# Converter_Dif-Se.net
KiCad netlist of a schematic drawn in Altium Designer
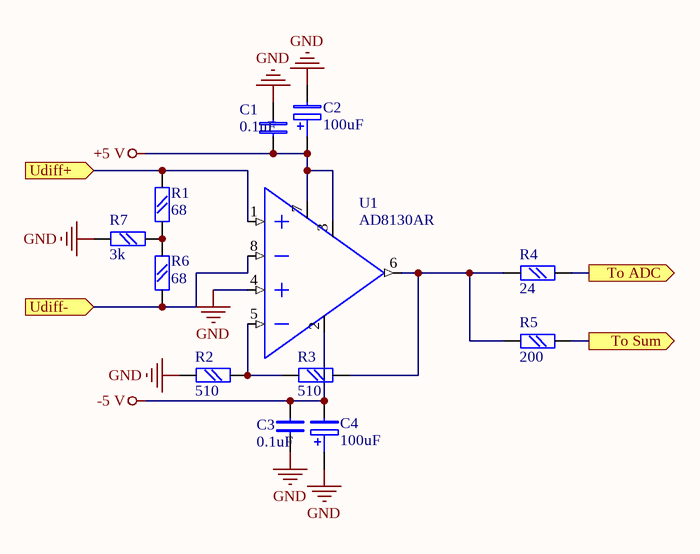
[diagram p0: Converter_Dif-Se.SchDoc]

(export (version "E")
  (design (tool "Eeschema 10.0.6"))
  (components
    (comp (ref "C1") (value "0.1uF") (footprint "chip0805") (libsource (lib "vDevice") (part "C")))
    (comp (ref "C2") (value "100uF") (footprint "CEL-SMD300") (libsource (lib "vDevice") (part "C POL")))
    (comp (ref "C3") (value "0.1uF") (footprint "chip0805") (libsource (lib "vDevice") (part "C")))
    (comp (ref "C4") (value "100uF") (footprint "CEL-SMD300") (libsource (lib "vDevice") (part "C POL")))
    (comp (ref "R1") (value "68") (footprint "chip0805") (libsource (lib "vDevice") (part "R")))
    (comp (ref "R2") (value "510") (footprint "chip0805") (libsource (lib "vDevice") (part "R")))
    (comp (ref "R3") (value "510") (footprint "chip0805") (libsource (lib "vDevice") (part "R")))
    (comp (ref "R4") (value "24") (footprint "chip0805") (libsource (lib "vDevice") (part "R")))
    (comp (ref "R5") (value "200") (footprint "chip0805") (libsource (lib "vDevice") (part "R")))
    (comp (ref "R6") (value "68") (footprint "chip0805") (libsource (lib "vDevice") (part "R")))
    (comp (ref "R7") (value "3k") (footprint "chip0805") (libsource (lib "vDevice") (part "R")))
    (comp (ref "U1") (value "AD8130AR") (footprint "SO-8") (libsource (lib "vAnalog") (part "AD8130")))
  )
  (nets
    (net (code "1") (name "+5 V") (class "Default")
      (node (ref "C1") (pin "2") (pinfunction "2_2") (pintype "passive"))
      (node (ref "C2") (pin "+") (pinfunction "+_+") (pintype "passive"))
      (node (ref "U1") (pin "3") (pinfunction "PD_3") (pintype "passive"))
      (node (ref "U1") (pin "7") (pinfunction "E+_7") (pintype "power_in"))
    )
    (net (code "2") (name "-5 V") (class "Default")
      (node (ref "C3") (pin "1") (pinfunction "1_1") (pintype "passive"))
      (node (ref "C4") (pin "-") (pinfunction "-_-") (pintype "passive"))
      (node (ref "U1") (pin "2") (pinfunction "E-_2") (pintype "power_in"))
    )
    (net (code "3") (name "/To ADC") (class "Default")
      (node (ref "R4") (pin "2") (pinfunction "2_2") (pintype "passive"))
    )
    (net (code "4") (name "/To Sum") (class "Default")
      (node (ref "R5") (pin "2") (pinfunction "2_2") (pintype "passive"))
    )
    (net (code "5") (name "/Udiff+") (class "Default")
      (node (ref "R1") (pin "1") (pinfunction "1_1") (pintype "passive"))
      (node (ref "U1") (pin "1") (pinfunction "+IN_1") (pintype "input"))
    )
    (net (code "6") (name "/Udiff-") (class "Default")
      (node (ref "R6") (pin "2") (pinfunction "2_2") (pintype "passive"))
      (node (ref "U1") (pin "8") (pinfunction "-IN_8") (pintype "input"))
    )
    (net (code "7") (name "GND") (class "Default")
      (node (ref "C1") (pin "1") (pinfunction "1_1") (pintype "passive"))
      (node (ref "C2") (pin "-") (pinfunction "-_-") (pintype "passive"))
      (node (ref "C3") (pin "2") (pinfunction "2_2") (pintype "passive"))
      (node (ref "C4") (pin "+") (pinfunction "+_+") (pintype "passive"))
      (node (ref "R2") (pin "1") (pinfunction "1_1") (pintype "passive"))
      (node (ref "R7") (pin "2") (pinfunction "2_2") (pintype "passive"))
      (node (ref "U1") (pin "4") (pinfunction "IN+_4") (pintype "input"))
    )
    (net (code "8") (name "Net-(R1-Pad2)") (class "Default")
      (node (ref "R1") (pin "2") (pinfunction "2_2") (pintype "passive"))
      (node (ref "R6") (pin "1") (pinfunction "1_1") (pintype "passive"))
      (node (ref "R7") (pin "1") (pinfunction "1_1") (pintype "passive"))
    )
    (net (code "9") (name "Net-(U1-IN-)") (class "Default")
      (node (ref "R2") (pin "2") (pinfunction "2_2") (pintype "passive"))
      (node (ref "R3") (pin "1") (pinfunction "1_1") (pintype "passive"))
      (node (ref "U1") (pin "5") (pinfunction "IN-_5") (pintype "input"))
    )
    (net (code "10") (name "Net-(U1-OUT)") (class "Default")
      (node (ref "R3") (pin "2") (pinfunction "2_2") (pintype "passive"))
      (node (ref "R4") (pin "1") (pinfunction "1_1") (pintype "passive"))
      (node (ref "R5") (pin "1") (pinfunction "1_1") (pintype "passive"))
      (node (ref "U1") (pin "6") (pinfunction "OUT_6") (pintype "output"))
    )
  )
)
